# receiver_mini_ra02.net
KiCad netlist of a schematic drawn in EAGLE
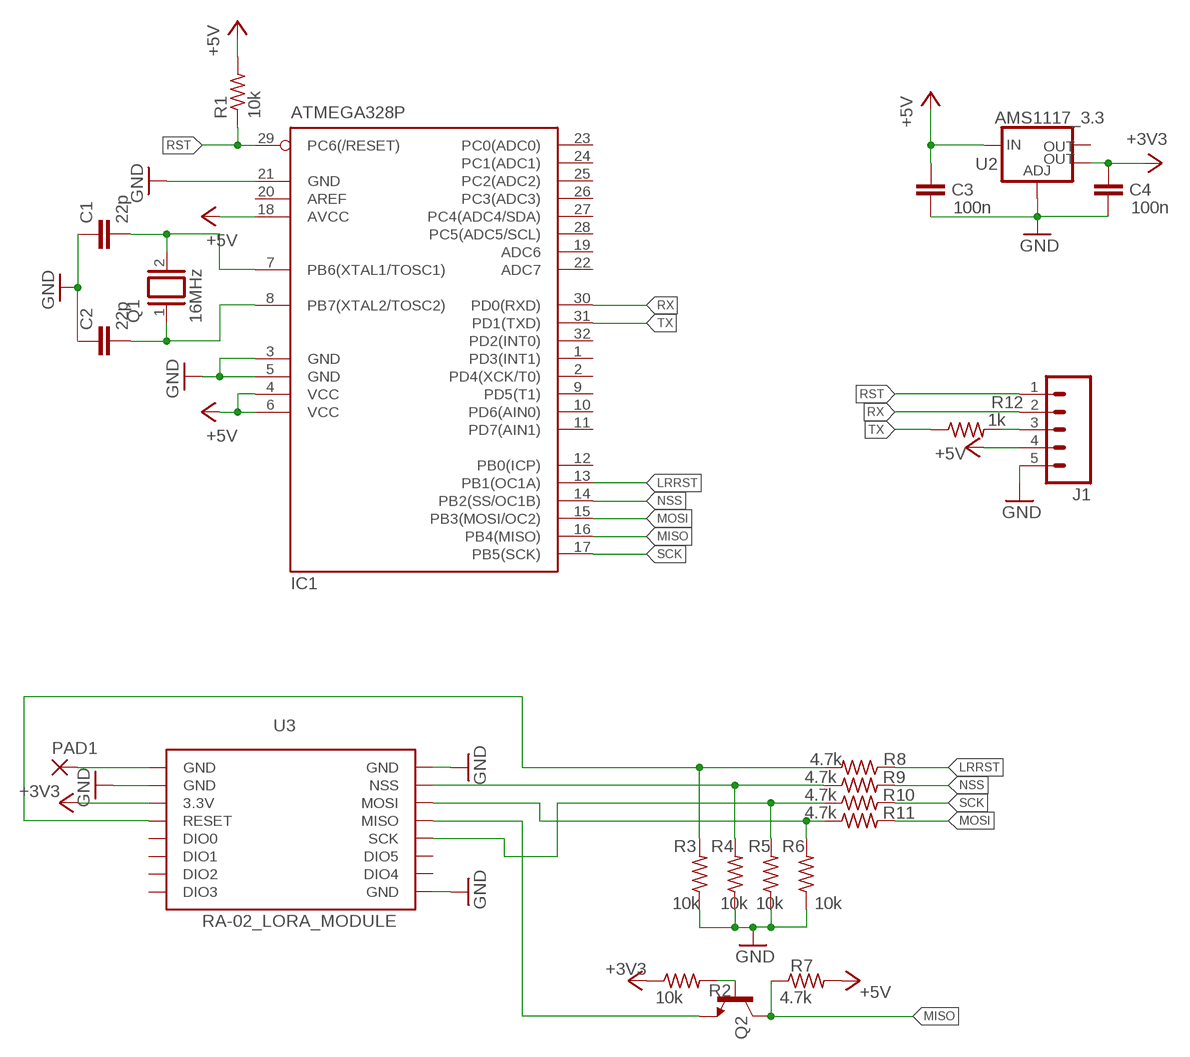
[diagram p0: schematic, sheet 1]

(export (version "E")
  (design (tool "Eeschema 10.0.6"))
  (components
    (comp (ref "C1")
      (value "22p")
      (footprint "eagle-import:C0805K")
      (libsource (lib "eagle-import") (part "C-EUC0805K"))
    )
    (comp (ref "C2")
      (value "22p")
      (footprint "eagle-import:C0805K")
      (libsource (lib "eagle-import") (part "C-EUC0805K"))
    )
    (comp (ref "C3")
      (value "100n")
      (footprint "eagle-import:C0805K")
      (libsource (lib "eagle-import") (part "C-EUC0805K"))
    )
    (comp (ref "C4")
      (value "100n")
      (footprint "eagle-import:C0805K")
      (libsource (lib "eagle-import") (part "C-EUC0805K"))
    )
    (comp (ref "IC1")
      (value "ATMEGA328P")
      (footprint "eagle-import:TQFP32-08")
      (fields (field (name "MPN") "ATMEGA8-16AU"))
      (libsource (lib "eagle-import") (part "MEGA8-AI"))
    )
    (comp (ref "J1")
      (value "M05PTH")
      (footprint "eagle-import:1X05")
      (libsource (lib "eagle-import") (part "M05PTH"))
    )
    (comp (ref "PAD1")
      (value "2,15/1,0")
      (footprint "eagle-import:2,15_1,0")
      (libsource (lib "eagle-import") (part "2,15/1,0"))
    )
    (comp (ref "Q1")
      (value "16MHz")
      (footprint "eagle-import:QS")
      (libsource (lib "eagle-import") (part "XTAL/S"))
    )
    (comp (ref "Q2")
      (value "BC817-16SMD")
      (footprint "eagle-import:SOT23-BEC")
      (libsource (lib "eagle-import") (part "BC817SMD-16"))
    )
    (comp (ref "R1")
      (value "10k")
      (footprint "eagle-import:R0805")
      (libsource (lib "eagle-import") (part "R-US_R0805"))
    )
    (comp (ref "R2")
      (value "10k")
      (footprint "eagle-import:R0805")
      (libsource (lib "eagle-import") (part "R-US_R0805"))
    )
    (comp (ref "R3")
      (value "10k")
      (footprint "eagle-import:R0805")
      (libsource (lib "eagle-import") (part "R-US_R0805"))
    )
    (comp (ref "R4")
      (value "10k")
      (footprint "eagle-import:R0805")
      (libsource (lib "eagle-import") (part "R-US_R0805"))
    )
    (comp (ref "R5")
      (value "10k")
      (footprint "eagle-import:R0805")
      (libsource (lib "eagle-import") (part "R-US_R0805"))
    )
    (comp (ref "R6")
      (value "10k")
      (footprint "eagle-import:R0805")
      (libsource (lib "eagle-import") (part "R-US_R0805"))
    )
    (comp (ref "R7")
      (value "4.7k")
      (footprint "eagle-import:R0805")
      (libsource (lib "eagle-import") (part "R-US_R0805"))
    )
    (comp (ref "R8")
      (value "4.7k")
      (footprint "eagle-import:R0805")
      (libsource (lib "eagle-import") (part "R-US_R0805"))
    )
    (comp (ref "R9")
      (value "4.7k")
      (footprint "eagle-import:R0805")
      (libsource (lib "eagle-import") (part "R-US_R0805"))
    )
    (comp (ref "R10")
      (value "4.7k")
      (footprint "eagle-import:R0805")
      (libsource (lib "eagle-import") (part "R-US_R0805"))
    )
    (comp (ref "R11")
      (value "4.7k")
      (footprint "eagle-import:R0805")
      (libsource (lib "eagle-import") (part "R-US_R0805"))
    )
    (comp (ref "R12")
      (value "1k")
      (footprint "eagle-import:R0805")
      (libsource (lib "eagle-import") (part "R-US_R0805"))
    )
    (comp (ref "U2")
      (value "AMS1117_3.3")
      (footprint "eagle-import:SOT223")
      (libsource (lib "eagle-import") (part "V_REG_LM1117SOT223"))
    )
    (comp (ref "U3")
      (value "RA-02_LORA_MODULE")
      (footprint "eagle-import:RA-02")
      (libsource (lib "eagle-import") (part "RA-02_LORA_MODULE"))
    )
  )
  (nets
    (net (code "1") (name "+3V3") (class "Default")
      (node (ref "C4") (pin "2") (pinfunction "2_2") (pintype "passive"))
      (node (ref "R2") (pin "1") (pinfunction "1_1") (pintype "passive"))
      (node (ref "U2") (pin "4") (pinfunction "OUT_4") (pintype "output"))
      (node (ref "U3") (pin "3.3V") (pinfunction "3.3V_3.3V") (pintype "power_in"))
    )
    (net (code "2") (name "+5V") (class "Default")
      (node (ref "C3") (pin "2") (pinfunction "2_2") (pintype "passive"))
      (node (ref "IC1") (pin "18") (pinfunction "AVCC_18") (pintype "power_in"))
      (node (ref "IC1") (pin "4") (pinfunction "VCC_4") (pintype "power_in"))
      (node (ref "IC1") (pin "6") (pinfunction "VCC_6") (pintype "power_in"))
      (node (ref "J1") (pin "4") (pinfunction "4_4") (pintype "passive"))
      (node (ref "R1") (pin "2") (pinfunction "2_2") (pintype "passive"))
      (node (ref "R7") (pin "2") (pinfunction "2_2") (pintype "passive"))
      (node (ref "U2") (pin "3") (pinfunction "IN_3") (pintype "input"))
    )
    (net (code "3") (name "GND") (class "Default")
      (node (ref "C1") (pin "1") (pinfunction "1_1") (pintype "passive"))
      (node (ref "C2") (pin "1") (pinfunction "1_1") (pintype "passive"))
      (node (ref "C3") (pin "1") (pinfunction "1_1") (pintype "passive"))
      (node (ref "C4") (pin "1") (pinfunction "1_1") (pintype "passive"))
      (node (ref "IC1") (pin "21") (pinfunction "GND_21") (pintype "power_in"))
      (node (ref "IC1") (pin "3") (pinfunction "GND_3") (pintype "power_in"))
      (node (ref "IC1") (pin "5") (pinfunction "GND_5") (pintype "power_in"))
      (node (ref "J1") (pin "5") (pinfunction "5_5") (pintype "passive"))
      (node (ref "R3") (pin "1") (pinfunction "1_1") (pintype "passive"))
      (node (ref "R4") (pin "1") (pinfunction "1_1") (pintype "passive"))
      (node (ref "R5") (pin "1") (pinfunction "1_1") (pintype "passive"))
      (node (ref "R6") (pin "1") (pinfunction "1_1") (pintype "passive"))
      (node (ref "U2") (pin "1") (pinfunction "ADJ_1") (pintype "input"))
      (node (ref "U3") (pin "GND@2") (pinfunction "GND_GND@2") (pintype "power_in"))
      (node (ref "U3") (pin "GND@3") (pinfunction "GND_GND@3") (pintype "power_in"))
      (node (ref "U3") (pin "GND@4") (pinfunction "GND_GND@4") (pintype "power_in"))
    )
    (net (code "4") (name "LRRST") (class "Default")
      (node (ref "IC1") (pin "13") (pinfunction "PB1(OC1A)_13") (pintype "bidirectional"))
      (node (ref "R8") (pin "1") (pinfunction "1_1") (pintype "passive"))
    )
    (net (code "5") (name "MISO") (class "Default")
      (node (ref "IC1") (pin "16") (pinfunction "PB4(MISO)_16") (pintype "bidirectional"))
      (node (ref "Q2") (pin "C") (pinfunction "C_C") (pintype "passive"))
      (node (ref "R7") (pin "1") (pinfunction "1_1") (pintype "passive"))
    )
    (net (code "6") (name "MOSI") (class "Default")
      (node (ref "IC1") (pin "15") (pinfunction "PB3(MOSI/OC2)_15") (pintype "bidirectional"))
      (node (ref "R11") (pin "2") (pinfunction "2_2") (pintype "passive"))
    )
    (net (code "7") (name "NSS") (class "Default")
      (node (ref "IC1") (pin "14") (pinfunction "PB2(SS/OC1B)_14") (pintype "bidirectional"))
      (node (ref "R9") (pin "2") (pinfunction "2_2") (pintype "passive"))
    )
    (net (code "8") (name "Net-(IC1-PB6(XTAL1{slash}TOSC1))") (class "Default")
      (node (ref "C1") (pin "2") (pinfunction "2_2") (pintype "passive"))
      (node (ref "IC1") (pin "7") (pinfunction "PB6(XTAL1/TOSC1)_7") (pintype "bidirectional"))
      (node (ref "Q1") (pin "2") (pinfunction "2_2") (pintype "passive"))
    )
    (net (code "9") (name "Net-(IC1-PB7(XTAL2{slash}TOSC2))") (class "Default")
      (node (ref "C2") (pin "2") (pinfunction "2_2") (pintype "passive"))
      (node (ref "IC1") (pin "8") (pinfunction "PB7(XTAL2/TOSC2)_8") (pintype "bidirectional"))
      (node (ref "Q1") (pin "1") (pinfunction "1_1") (pintype "passive"))
    )
    (net (code "10") (name "Net-(J1-Pad3)") (class "Default")
      (node (ref "J1") (pin "3") (pinfunction "3_3") (pintype "passive"))
      (node (ref "R12") (pin "2") (pinfunction "2_2") (pintype "passive"))
    )
    (net (code "11") (name "Net-(PAD1-P)") (class "Default")
      (node (ref "PAD1") (pin "1") (pinfunction "P_1") (pintype "passive"))
      (node (ref "U3") (pin "GND") (pinfunction "GND_GND") (pintype "power_in"))
    )
    (net (code "12") (name "Net-(Q2-PadB)") (class "Default")
      (node (ref "Q2") (pin "B") (pinfunction "B_B") (pintype "passive"))
      (node (ref "R2") (pin "2") (pinfunction "2_2") (pintype "passive"))
    )
    (net (code "13") (name "Net-(Q2-PadE)") (class "Default")
      (node (ref "Q2") (pin "E") (pinfunction "E_E") (pintype "passive"))
      (node (ref "U3") (pin "MISO") (pinfunction "MISO_MISO") (pintype "bidirectional"))
    )
    (net (code "14") (name "Net-(R3-Pad2)") (class "Default")
      (node (ref "R3") (pin "2") (pinfunction "2_2") (pintype "passive"))
      (node (ref "R8") (pin "2") (pinfunction "2_2") (pintype "passive"))
      (node (ref "U3") (pin "RESET") (pinfunction "RESET_RESET") (pintype "bidirectional"))
    )
    (net (code "15") (name "Net-(R4-Pad2)") (class "Default")
      (node (ref "R4") (pin "2") (pinfunction "2_2") (pintype "passive"))
      (node (ref "R9") (pin "1") (pinfunction "1_1") (pintype "passive"))
      (node (ref "U3") (pin "NSS") (pinfunction "NSS_NSS") (pintype "bidirectional"))
    )
    (net (code "16") (name "Net-(R10-Pad1)") (class "Default")
      (node (ref "R10") (pin "1") (pinfunction "1_1") (pintype "passive"))
      (node (ref "R5") (pin "2") (pinfunction "2_2") (pintype "passive"))
      (node (ref "U3") (pin "SCK") (pinfunction "SCK_SCK") (pintype "bidirectional"))
    )
    (net (code "17") (name "Net-(R11-Pad1)") (class "Default")
      (node (ref "R11") (pin "1") (pinfunction "1_1") (pintype "passive"))
      (node (ref "R6") (pin "2") (pinfunction "2_2") (pintype "passive"))
      (node (ref "U3") (pin "MOSI") (pinfunction "MOSI_MOSI") (pintype "bidirectional"))
    )
    (net (code "18") (name "RST") (class "Default")
      (node (ref "IC1") (pin "29") (pinfunction "PC6(/RESET)_29") (pintype "bidirectional"))
      (node (ref "J1") (pin "1") (pinfunction "1_1") (pintype "passive"))
      (node (ref "R1") (pin "1") (pinfunction "1_1") (pintype "passive"))
    )
    (net (code "19") (name "RX") (class "Default")
      (node (ref "IC1") (pin "30") (pinfunction "PD0(RXD)_30") (pintype "bidirectional"))
      (node (ref "J1") (pin "2") (pinfunction "2_2") (pintype "passive"))
    )
    (net (code "20") (name "SCK") (class "Default")
      (node (ref "IC1") (pin "17") (pinfunction "PB5(SCK)_17") (pintype "bidirectional"))
      (node (ref "R10") (pin "2") (pinfunction "2_2") (pintype "passive"))
    )
    (net (code "21") (name "TX") (class "Default")
      (node (ref "IC1") (pin "31") (pinfunction "PD1(TXD)_31") (pintype "bidirectional"))
      (node (ref "R12") (pin "1") (pinfunction "1_1") (pintype "passive"))
    )
    (net (code "22") (name "unconnected-(IC1-ADC6-Pad19)") (class "Default")
      (node (ref "IC1") (pin "19") (pinfunction "ADC6_19") (pintype "bidirectional"))
    )
    (net (code "23") (name "unconnected-(IC1-ADC7-Pad22)") (class "Default")
      (node (ref "IC1") (pin "22") (pinfunction "ADC7_22") (pintype "bidirectional"))
    )
    (net (code "24") (name "unconnected-(IC1-AREF-Pad20)") (class "Default")
      (node (ref "IC1") (pin "20") (pinfunction "AREF_20") (pintype "passive"))
    )
    (net (code "25") (name "unconnected-(IC1-PB0(ICP)-Pad12)") (class "Default")
      (node (ref "IC1") (pin "12") (pinfunction "PB0(ICP)_12") (pintype "bidirectional"))
    )
    (net (code "26") (name "unconnected-(IC1-PC0(ADC0)-Pad23)") (class "Default")
      (node (ref "IC1") (pin "23") (pinfunction "PC0(ADC0)_23") (pintype "bidirectional"))
    )
    (net (code "27") (name "unconnected-(IC1-PC1(ADC1)-Pad24)") (class "Default")
      (node (ref "IC1") (pin "24") (pinfunction "PC1(ADC1)_24") (pintype "bidirectional"))
    )
    (net (code "28") (name "unconnected-(IC1-PC2(ADC2)-Pad25)") (class "Default")
      (node (ref "IC1") (pin "25") (pinfunction "PC2(ADC2)_25") (pintype "bidirectional"))
    )
    (net (code "29") (name "unconnected-(IC1-PC3(ADC3)-Pad26)") (class "Default")
      (node (ref "IC1") (pin "26") (pinfunction "PC3(ADC3)_26") (pintype "bidirectional"))
    )
    (net (code "30") (name "unconnected-(IC1-PC4(ADC4{slash}SDA)-Pad27)") (class "Default")
      (node (ref "IC1") (pin "27") (pinfunction "PC4(ADC4/SDA)_27") (pintype "bidirectional"))
    )
    (net (code "31") (name "unconnected-(IC1-PC5(ADC5{slash}SCL)-Pad28)") (class "Default")
      (node (ref "IC1") (pin "28") (pinfunction "PC5(ADC5/SCL)_28") (pintype "bidirectional"))
    )
    (net (code "32") (name "unconnected-(IC1-PD2(INT0)-Pad32)") (class "Default")
      (node (ref "IC1") (pin "32") (pinfunction "PD2(INT0)_32") (pintype "bidirectional"))
    )
    (net (code "33") (name "unconnected-(IC1-PD3(INT1)-Pad1)") (class "Default")
      (node (ref "IC1") (pin "1") (pinfunction "PD3(INT1)_1") (pintype "bidirectional"))
    )
    (net (code "34") (name "unconnected-(IC1-PD4(XCK{slash}T0)-Pad2)") (class "Default")
      (node (ref "IC1") (pin "2") (pinfunction "PD4(XCK/T0)_2") (pintype "bidirectional"))
    )
    (net (code "35") (name "unconnected-(IC1-PD5(T1)-Pad9)") (class "Default")
      (node (ref "IC1") (pin "9") (pinfunction "PD5(T1)_9") (pintype "bidirectional"))
    )
    (net (code "36") (name "unconnected-(IC1-PD6(AIN0)-Pad10)") (class "Default")
      (node (ref "IC1") (pin "10") (pinfunction "PD6(AIN0)_10") (pintype "bidirectional"))
    )
    (net (code "37") (name "unconnected-(IC1-PD7(AIN1)-Pad11)") (class "Default")
      (node (ref "IC1") (pin "11") (pinfunction "PD7(AIN1)_11") (pintype "bidirectional"))
    )
    (net (code "38") (name "unconnected-(U2-OUT-Pad2)") (class "Default")
      (node (ref "U2") (pin "2") (pinfunction "OUT_2") (pintype "output"))
    )
    (net (code "39") (name "unconnected-(U3-PadDIO0)") (class "Default")
      (node (ref "U3") (pin "DIO0") (pinfunction "DIO0_DIO0") (pintype "bidirectional"))
    )
    (net (code "40") (name "unconnected-(U3-PadDIO1)") (class "Default")
      (node (ref "U3") (pin "DIO1") (pinfunction "DIO1_DIO1") (pintype "bidirectional"))
    )
    (net (code "41") (name "unconnected-(U3-PadDIO2)") (class "Default")
      (node (ref "U3") (pin "DIO2") (pinfunction "DIO2_DIO2") (pintype "bidirectional"))
    )
    (net (code "42") (name "unconnected-(U3-PadDIO3)") (class "Default")
      (node (ref "U3") (pin "DIO3") (pinfunction "DIO3_DIO3") (pintype "bidirectional"))
    )
    (net (code "43") (name "unconnected-(U3-PadDIO4)") (class "Default")
      (node (ref "U3") (pin "DIO4") (pinfunction "DIO4_DIO4") (pintype "bidirectional"))
    )
    (net (code "44") (name "unconnected-(U3-PadDIO5)") (class "Default")
      (node (ref "U3") (pin "DIO5") (pinfunction "DIO5_DIO5") (pintype "bidirectional"))
    )
  )
)
